# Connectors.net
KiCad netlist of a schematic drawn in Altium Designer
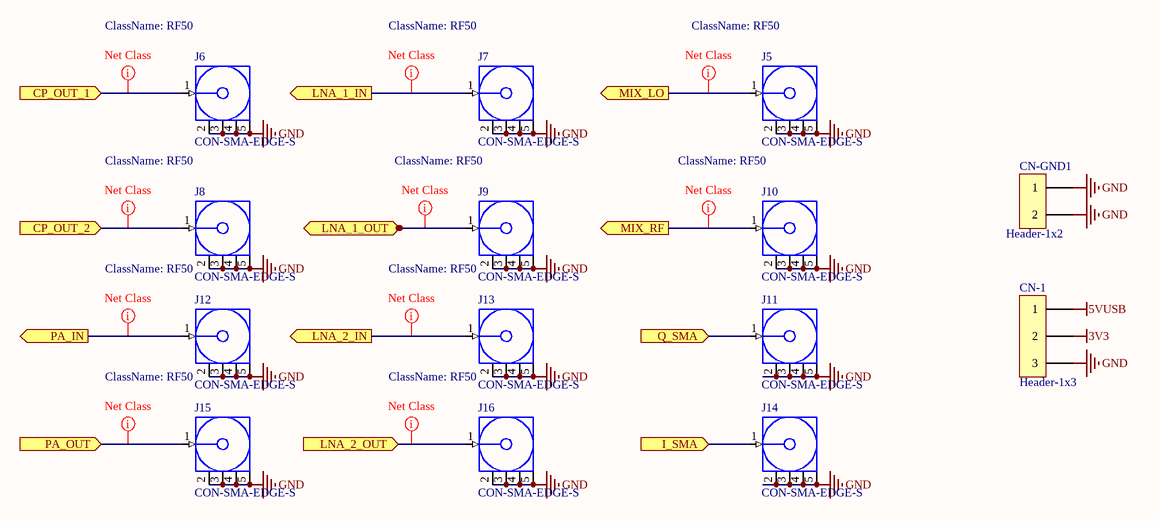
[diagram p0: Connectors.SchDoc]

(export (version "E")
  (design (tool "Eeschema 10.0.6"))
  (components
    (comp (ref "CN-1")
      (value "Header-1x3")
      (footprint "Header-1x3-Jumper")
      (libsource (lib "B105lib") (part "Header-1x3"))
    )
    (comp (ref "CN-GND1")
      (value "Header-1x2")
      (footprint "HEADER-1x2-Jumper")
      (libsource (lib "B105lib") (part "Header-1x2"))
    )
    (comp (ref "J5")
      (value "CON-SMA-EDGE-S")
      (footprint "CON-SMA-EDGE-S")
      (description "CONN SMA JACK STR EDGE MNT")
      (fields (field (name "MANUFACTURER") "RF Solutions"))
      (libsource (lib "Schlib1") (part "CON-SMA-EDGE-S"))
    )
    (comp (ref "J6")
      (value "CON-SMA-EDGE-S")
      (footprint "CON-SMA-EDGE-S")
      (description "CONN SMA JACK STR EDGE MNT")
      (fields (field (name "MANUFACTURER") "RF Solutions"))
      (libsource (lib "Schlib1") (part "CON-SMA-EDGE-S"))
    )
    (comp (ref "J7")
      (value "CON-SMA-EDGE-S")
      (footprint "CON-SMA-EDGE-S")
      (description "CONN SMA JACK STR EDGE MNT")
      (fields (field (name "MANUFACTURER") "RF Solutions"))
      (libsource (lib "Schlib1") (part "CON-SMA-EDGE-S"))
    )
    (comp (ref "J8")
      (value "CON-SMA-EDGE-S")
      (footprint "CON-SMA-EDGE-S")
      (description "CONN SMA JACK STR EDGE MNT")
      (fields (field (name "MANUFACTURER") "RF Solutions"))
      (libsource (lib "Schlib1") (part "CON-SMA-EDGE-S"))
    )
    (comp (ref "J9")
      (value "CON-SMA-EDGE-S")
      (footprint "CON-SMA-EDGE-S")
      (description "CONN SMA JACK STR EDGE MNT")
      (fields (field (name "MANUFACTURER") "RF Solutions"))
      (libsource (lib "Schlib1") (part "CON-SMA-EDGE-S"))
    )
    (comp (ref "J10")
      (value "CON-SMA-EDGE-S")
      (footprint "CON-SMA-EDGE-S")
      (description "CONN SMA JACK STR EDGE MNT")
      (fields (field (name "MANUFACTURER") "RF Solutions"))
      (libsource (lib "Schlib1") (part "CON-SMA-EDGE-S"))
    )
    (comp (ref "J11")
      (value "CON-SMA-EDGE-S")
      (footprint "CON-SMA-EDGE-S")
      (description "CONN SMA JACK STR EDGE MNT")
      (fields (field (name "MANUFACTURER") "RF Solutions"))
      (libsource (lib "Schlib1") (part "CON-SMA-EDGE-S"))
    )
    (comp (ref "J12")
      (value "CON-SMA-EDGE-S")
      (footprint "CON-SMA-EDGE-S")
      (description "CONN SMA JACK STR EDGE MNT")
      (fields (field (name "MANUFACTURER") "RF Solutions"))
      (libsource (lib "Schlib1") (part "CON-SMA-EDGE-S"))
    )
    (comp (ref "J13")
      (value "CON-SMA-EDGE-S")
      (footprint "CON-SMA-EDGE-S")
      (description "CONN SMA JACK STR EDGE MNT")
      (fields (field (name "MANUFACTURER") "RF Solutions"))
      (libsource (lib "Schlib1") (part "CON-SMA-EDGE-S"))
    )
    (comp (ref "J14")
      (value "CON-SMA-EDGE-S")
      (footprint "CON-SMA-EDGE-S")
      (description "CONN SMA JACK STR EDGE MNT")
      (fields (field (name "MANUFACTURER") "RF Solutions"))
      (libsource (lib "Schlib1") (part "CON-SMA-EDGE-S"))
    )
    (comp (ref "J15")
      (value "CON-SMA-EDGE-S")
      (footprint "CON-SMA-EDGE-S")
      (description "CONN SMA JACK STR EDGE MNT")
      (fields (field (name "MANUFACTURER") "RF Solutions"))
      (libsource (lib "Schlib1") (part "CON-SMA-EDGE-S"))
    )
    (comp (ref "J16")
      (value "CON-SMA-EDGE-S")
      (footprint "CON-SMA-EDGE-S")
      (description "CONN SMA JACK STR EDGE MNT")
      (fields (field (name "MANUFACTURER") "RF Solutions"))
      (libsource (lib "Schlib1") (part "CON-SMA-EDGE-S"))
    )
  )
  (nets
    (net (code "1") (name "/CP_OUT_1") (class "Default")
      (node (ref "J6") (pin "1") (pinfunction "Signal_1") (pintype "input"))
    )
    (net (code "2") (name "/CP_OUT_2") (class "Default")
      (node (ref "J8") (pin "1") (pinfunction "Signal_1") (pintype "input"))
    )
    (net (code "3") (name "/I_SMA") (class "Default")
      (node (ref "J14") (pin "1") (pinfunction "Signal_1") (pintype "input"))
    )
    (net (code "4") (name "/LNA_1_IN") (class "Default")
      (node (ref "J7") (pin "1") (pinfunction "Signal_1") (pintype "input"))
    )
    (net (code "5") (name "/LNA_1_OUT") (class "Default")
      (node (ref "J9") (pin "1") (pinfunction "Signal_1") (pintype "input"))
    )
    (net (code "6") (name "/LNA_2_IN") (class "Default")
      (node (ref "J13") (pin "1") (pinfunction "Signal_1") (pintype "input"))
    )
    (net (code "7") (name "/LNA_2_OUT") (class "Default")
      (node (ref "J16") (pin "1") (pinfunction "Signal_1") (pintype "input"))
    )
    (net (code "8") (name "/MIX_LO") (class "Default")
      (node (ref "J5") (pin "1") (pinfunction "Signal_1") (pintype "input"))
    )
    (net (code "9") (name "/MIX_RF") (class "Default")
      (node (ref "J10") (pin "1") (pinfunction "Signal_1") (pintype "input"))
    )
    (net (code "10") (name "/PA_IN") (class "Default")
      (node (ref "J12") (pin "1") (pinfunction "Signal_1") (pintype "input"))
    )
    (net (code "11") (name "/PA_OUT") (class "Default")
      (node (ref "J15") (pin "1") (pinfunction "Signal_1") (pintype "input"))
    )
    (net (code "12") (name "/Q_SMA") (class "Default")
      (node (ref "J11") (pin "1") (pinfunction "Signal_1") (pintype "input"))
    )
    (net (code "13") (name "3V3") (class "Default")
      (node (ref "CN-1") (pin "2") (pinfunction "2_2") (pintype "passive"))
    )
    (net (code "14") (name "5VUSB") (class "Default")
      (node (ref "CN-1") (pin "1") (pinfunction "1_1") (pintype "passive"))
    )
    (net (code "15") (name "GND") (class "Default")
      (node (ref "CN-1") (pin "3") (pinfunction "3_3") (pintype "passive"))
      (node (ref "CN-GND1") (pin "1") (pinfunction "1_1") (pintype "passive"))
      (node (ref "CN-GND1") (pin "2") (pinfunction "2_2") (pintype "passive"))
      (node (ref "J10") (pin "2") (pinfunction "GND_2") (pintype "power_in"))
      (node (ref "J10") (pin "3") (pinfunction "GND_3") (pintype "power_in"))
      (node (ref "J10") (pin "4") (pinfunction "GND_4") (pintype "power_in"))
      (node (ref "J10") (pin "5") (pinfunction "GND_5") (pintype "power_in"))
      (node (ref "J11") (pin "2") (pinfunction "GND_2") (pintype "power_in"))
      (node (ref "J11") (pin "3") (pinfunction "GND_3") (pintype "power_in"))
      (node (ref "J11") (pin "4") (pinfunction "GND_4") (pintype "power_in"))
      (node (ref "J11") (pin "5") (pinfunction "GND_5") (pintype "power_in"))
      (node (ref "J12") (pin "2") (pinfunction "GND_2") (pintype "power_in"))
      (node (ref "J12") (pin "3") (pinfunction "GND_3") (pintype "power_in"))
      (node (ref "J12") (pin "4") (pinfunction "GND_4") (pintype "power_in"))
      (node (ref "J12") (pin "5") (pinfunction "GND_5") (pintype "power_in"))
      (node (ref "J13") (pin "2") (pinfunction "GND_2") (pintype "power_in"))
      (node (ref "J13") (pin "3") (pinfunction "GND_3") (pintype "power_in"))
      (node (ref "J13") (pin "4") (pinfunction "GND_4") (pintype "power_in"))
      (node (ref "J13") (pin "5") (pinfunction "GND_5") (pintype "power_in"))
      (node (ref "J14") (pin "2") (pinfunction "GND_2") (pintype "power_in"))
      (node (ref "J14") (pin "3") (pinfunction "GND_3") (pintype "power_in"))
      (node (ref "J14") (pin "4") (pinfunction "GND_4") (pintype "power_in"))
      (node (ref "J14") (pin "5") (pinfunction "GND_5") (pintype "power_in"))
      (node (ref "J15") (pin "2") (pinfunction "GND_2") (pintype "power_in"))
      (node (ref "J15") (pin "3") (pinfunction "GND_3") (pintype "power_in"))
      (node (ref "J15") (pin "4") (pinfunction "GND_4") (pintype "power_in"))
      (node (ref "J15") (pin "5") (pinfunction "GND_5") (pintype "power_in"))
      (node (ref "J16") (pin "2") (pinfunction "GND_2") (pintype "power_in"))
      (node (ref "J16") (pin "3") (pinfunction "GND_3") (pintype "power_in"))
      (node (ref "J16") (pin "4") (pinfunction "GND_4") (pintype "power_in"))
      (node (ref "J16") (pin "5") (pinfunction "GND_5") (pintype "power_in"))
      (node (ref "J5") (pin "2") (pinfunction "GND_2") (pintype "power_in"))
      (node (ref "J5") (pin "3") (pinfunction "GND_3") (pintype "power_in"))
      (node (ref "J5") (pin "4") (pinfunction "GND_4") (pintype "power_in"))
      (node (ref "J5") (pin "5") (pinfunction "GND_5") (pintype "power_in"))
      (node (ref "J6") (pin "2") (pinfunction "GND_2") (pintype "power_in"))
      (node (ref "J6") (pin "3") (pinfunction "GND_3") (pintype "power_in"))
      (node (ref "J6") (pin "4") (pinfunction "GND_4") (pintype "power_in"))
      (node (ref "J6") (pin "5") (pinfunction "GND_5") (pintype "power_in"))
      (node (ref "J7") (pin "2") (pinfunction "GND_2") (pintype "power_in"))
      (node (ref "J7") (pin "3") (pinfunction "GND_3") (pintype "power_in"))
      (node (ref "J7") (pin "4") (pinfunction "GND_4") (pintype "power_in"))
      (node (ref "J7") (pin "5") (pinfunction "GND_5") (pintype "power_in"))
      (node (ref "J8") (pin "2") (pinfunction "GND_2") (pintype "power_in"))
      (node (ref "J8") (pin "3") (pinfunction "GND_3") (pintype "power_in"))
      (node (ref "J8") (pin "4") (pinfunction "GND_4") (pintype "power_in"))
      (node (ref "J8") (pin "5") (pinfunction "GND_5") (pintype "power_in"))
      (node (ref "J9") (pin "2") (pinfunction "GND_2") (pintype "power_in"))
      (node (ref "J9") (pin "3") (pinfunction "GND_3") (pintype "power_in"))
      (node (ref "J9") (pin "4") (pinfunction "GND_4") (pintype "power_in"))
      (node (ref "J9") (pin "5") (pinfunction "GND_5") (pintype "power_in"))
    )
  )
)
